# inclinometer-lcd-backpack.net
KiCad netlist of a schematic drawn in EAGLE
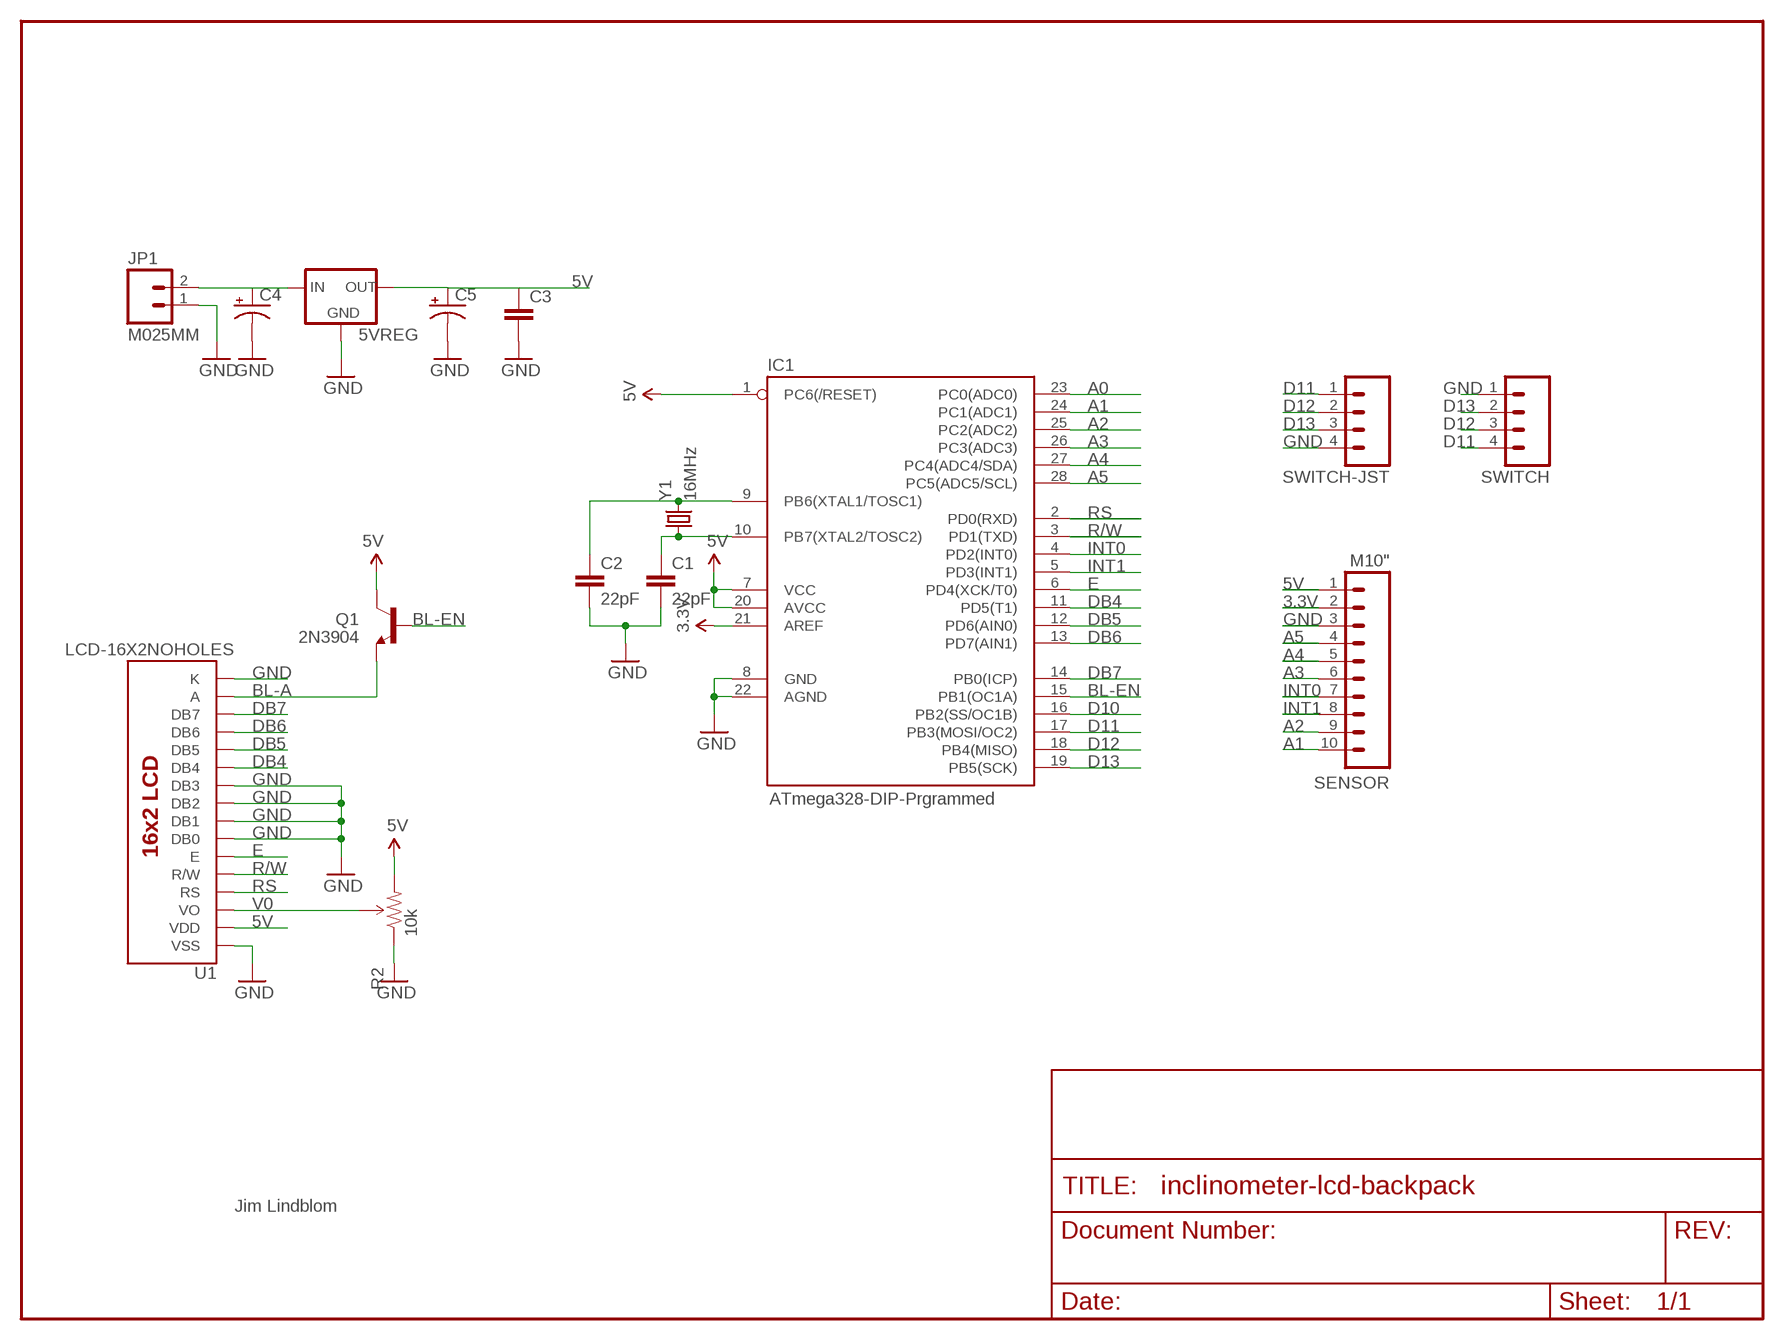
[diagram p0: schematic, sheet 1]

(export (version "E")
  (design (tool "Eeschema 10.0.6"))
  (components
    (comp (ref "5VREG")
      (value "78XXS")
      (footprint "eagle-import:78XXS")
      (libsource (lib "eagle-import") (part "78XXS"))
    )
    (comp (ref "C1")
      (value "22pF")
      (footprint "eagle-import:CAP-PTH-SMALL2")
      (libsource (lib "eagle-import") (part "CAPPTH2"))
    )
    (comp (ref "C2")
      (value "22pF")
      (footprint "eagle-import:CAP-PTH-SMALL2")
      (libsource (lib "eagle-import") (part "CAPPTH2"))
    )
    (comp (ref "C3")
      (value "CAPPTH2")
      (footprint "eagle-import:CAP-PTH-SMALL2")
      (libsource (lib "eagle-import") (part "SparkFun-Capacitors_CAPPTH2"))
    )
    (comp (ref "C4")
      (value "CAP_POLPTH2")
      (footprint "eagle-import:CPOL-RADIAL-10UF-25V")
      (libsource (lib "eagle-import") (part "CAP_POLPTH2"))
    )
    (comp (ref "C5")
      (value "CAP_POLPTH2")
      (footprint "eagle-import:CPOL-RADIAL-10UF-25V")
      (libsource (lib "eagle-import") (part "CAP_POLPTH2"))
    )
    (comp (ref "IC1")
      (value "ATmega328-DIP-Prgrammed")
      (footprint "eagle-import:DIL28-3")
      (libsource (lib "eagle-import") (part "AVR-MEGA8-PPTH"))
    )
    (comp (ref "JP1")
      (value "M025MM")
      (footprint "eagle-import:SCREWTERMINAL-5MM-2")
      (libsource (lib "eagle-import") (part "M025MM"))
    )
    (comp (ref "Q1")
      (value "2N3904")
      (footprint "eagle-import:TO-92")
      (libsource (lib "eagle-import") (part "TRANSISTOR_NPNTO92"))
    )
    (comp (ref "R2")
      (value "10k")
      (footprint "eagle-import:TRIM_POT_PTH")
      (libsource (lib "eagle-import") (part "TRIMPOTPTH"))
    )
    (comp (ref "SENSOR")
      (value "M10\"")
      (footprint "eagle-import:1X10")
      (libsource (lib "eagle-import") (part "M10{dblquote}"))
    )
    (comp (ref "SWITCH")
      (value "M04PTH")
      (footprint "eagle-import:1X04")
      (libsource (lib "eagle-import") (part "M04PTH"))
    )
    (comp (ref "SWITCH-JST")
      (value "M04JST-PTH")
      (footprint "eagle-import:JST-4-PTH")
      (libsource (lib "eagle-import") (part "M04JST-PTH"))
    )
    (comp (ref "U1")
      (value "LCD-16X2NOHOLES")
      (footprint "eagle-import:LCD-16X2_NOHOLES")
      (libsource (lib "eagle-import") (part "LCD-16X2NOHOLES"))
    )
    (comp (ref "Y1")
      (value "16MHz")
      (footprint "eagle-import:HC49US")
      (libsource (lib "eagle-import") (part "CRYSTALHC49US"))
    )
  )
  (nets
    (net (code "1") (name "/A0") (class "Default")
      (node (ref "IC1") (pin "23") (pinfunction "PC0(ADC0)_23") (pintype "bidirectional"))
    )
    (net (code "2") (name "/A1") (class "Default")
      (node (ref "IC1") (pin "24") (pinfunction "PC1(ADC1)_24") (pintype "bidirectional"))
      (node (ref "SENSOR") (pin "10") (pinfunction "10_10") (pintype "passive"))
    )
    (net (code "3") (name "/A2") (class "Default")
      (node (ref "IC1") (pin "25") (pinfunction "PC2(ADC2)_25") (pintype "bidirectional"))
      (node (ref "SENSOR") (pin "9") (pinfunction "9_9") (pintype "passive"))
    )
    (net (code "4") (name "/A3") (class "Default")
      (node (ref "IC1") (pin "26") (pinfunction "PC3(ADC3)_26") (pintype "bidirectional"))
      (node (ref "SENSOR") (pin "6") (pinfunction "6_6") (pintype "passive"))
    )
    (net (code "5") (name "/A4") (class "Default")
      (node (ref "IC1") (pin "27") (pinfunction "PC4(ADC4/SDA)_27") (pintype "bidirectional"))
      (node (ref "SENSOR") (pin "5") (pinfunction "5_5") (pintype "passive"))
    )
    (net (code "6") (name "/A5") (class "Default")
      (node (ref "IC1") (pin "28") (pinfunction "PC5(ADC5/SCL)_28") (pintype "bidirectional"))
      (node (ref "SENSOR") (pin "4") (pinfunction "4_4") (pintype "passive"))
    )
    (net (code "7") (name "/BL-A") (class "Default")
      (node (ref "Q1") (pin "1") (pinfunction "E_1") (pintype "passive"))
      (node (ref "U1") (pin "15") (pinfunction "A_15") (pintype "power_in"))
    )
    (net (code "8") (name "/BL-EN") (class "Default")
      (node (ref "IC1") (pin "15") (pinfunction "PB1(OC1A)_15") (pintype "bidirectional"))
      (node (ref "Q1") (pin "2") (pinfunction "B_2") (pintype "passive"))
    )
    (net (code "9") (name "/D10") (class "Default")
      (node (ref "IC1") (pin "16") (pinfunction "PB2(SS/OC1B)_16") (pintype "bidirectional"))
    )
    (net (code "10") (name "/D11") (class "Default")
      (node (ref "IC1") (pin "17") (pinfunction "PB3(MOSI/OC2)_17") (pintype "bidirectional"))
      (node (ref "SWITCH") (pin "4") (pinfunction "4_4") (pintype "passive"))
      (node (ref "SWITCH-JST") (pin "1") (pinfunction "1_1") (pintype "passive"))
    )
    (net (code "11") (name "/D12") (class "Default")
      (node (ref "IC1") (pin "18") (pinfunction "PB4(MISO)_18") (pintype "bidirectional"))
      (node (ref "SWITCH") (pin "3") (pinfunction "3_3") (pintype "passive"))
      (node (ref "SWITCH-JST") (pin "2") (pinfunction "2_2") (pintype "passive"))
    )
    (net (code "12") (name "/D13") (class "Default")
      (node (ref "IC1") (pin "19") (pinfunction "PB5(SCK)_19") (pintype "bidirectional"))
      (node (ref "SWITCH") (pin "2") (pinfunction "2_2") (pintype "passive"))
      (node (ref "SWITCH-JST") (pin "3") (pinfunction "3_3") (pintype "passive"))
    )
    (net (code "13") (name "/DB4") (class "Default")
      (node (ref "IC1") (pin "11") (pinfunction "PD5(T1)_11") (pintype "bidirectional"))
      (node (ref "U1") (pin "11") (pinfunction "DB4_11") (pintype "bidirectional"))
    )
    (net (code "14") (name "/DB5") (class "Default")
      (node (ref "IC1") (pin "12") (pinfunction "PD6(AIN0)_12") (pintype "bidirectional"))
      (node (ref "U1") (pin "12") (pinfunction "DB5_12") (pintype "bidirectional"))
    )
    (net (code "15") (name "/DB6") (class "Default")
      (node (ref "IC1") (pin "13") (pinfunction "PD7(AIN1)_13") (pintype "bidirectional"))
      (node (ref "U1") (pin "13") (pinfunction "DB6_13") (pintype "bidirectional"))
    )
    (net (code "16") (name "/DB7") (class "Default")
      (node (ref "IC1") (pin "14") (pinfunction "PB0(ICP)_14") (pintype "bidirectional"))
      (node (ref "U1") (pin "14") (pinfunction "DB7_14") (pintype "bidirectional"))
    )
    (net (code "17") (name "/E") (class "Default")
      (node (ref "IC1") (pin "6") (pinfunction "PD4(XCK/T0)_6") (pintype "bidirectional"))
      (node (ref "U1") (pin "6") (pinfunction "E_6") (pintype "input"))
    )
    (net (code "18") (name "/INT0") (class "Default")
      (node (ref "IC1") (pin "4") (pinfunction "PD2(INT0)_4") (pintype "bidirectional"))
      (node (ref "SENSOR") (pin "7") (pinfunction "7_7") (pintype "passive"))
    )
    (net (code "19") (name "/INT1") (class "Default")
      (node (ref "IC1") (pin "5") (pinfunction "PD3(INT1)_5") (pintype "bidirectional"))
      (node (ref "SENSOR") (pin "8") (pinfunction "8_8") (pintype "passive"))
    )
    (net (code "20") (name "/RS") (class "Default")
      (node (ref "IC1") (pin "2") (pinfunction "PD0(RXD)_2") (pintype "bidirectional"))
      (node (ref "U1") (pin "4") (pinfunction "RS_4") (pintype "input"))
    )
    (net (code "21") (name "/R{slash}W") (class "Default")
      (node (ref "IC1") (pin "3") (pinfunction "PD1(TXD)_3") (pintype "bidirectional"))
      (node (ref "U1") (pin "5") (pinfunction "R/W_5") (pintype "input"))
    )
    (net (code "22") (name "/V0") (class "Default")
      (node (ref "R2") (pin "2") (pinfunction "WIPER_2") (pintype "passive"))
      (node (ref "U1") (pin "3") (pinfunction "VO_3") (pintype "bidirectional"))
    )
    (net (code "23") (name "3.3V") (class "Default")
      (node (ref "IC1") (pin "21") (pinfunction "AREF_21") (pintype "bidirectional"))
      (node (ref "SENSOR") (pin "2") (pinfunction "2_2") (pintype "passive"))
    )
    (net (code "24") (name "5V") (class "Default")
      (node (ref "5VREG") (pin "OUT") (pinfunction "OUT_OUT") (pintype "passive"))
      (node (ref "C3") (pin "1") (pinfunction "1_1") (pintype "passive"))
      (node (ref "C5") (pin "1") (pinfunction "+_1") (pintype "passive"))
      (node (ref "IC1") (pin "1") (pinfunction "PC6(/RESET)_1") (pintype "bidirectional"))
      (node (ref "IC1") (pin "20") (pinfunction "AVCC_20") (pintype "bidirectional"))
      (node (ref "IC1") (pin "7") (pinfunction "VCC_7") (pintype "bidirectional"))
      (node (ref "Q1") (pin "3") (pinfunction "C_3") (pintype "passive"))
      (node (ref "R2") (pin "3") (pinfunction "CW_3") (pintype "passive"))
      (node (ref "SENSOR") (pin "1") (pinfunction "1_1") (pintype "passive"))
      (node (ref "U1") (pin "2") (pinfunction "VDD_2") (pintype "power_in"))
    )
    (net (code "25") (name "GND") (class "Default")
      (node (ref "5VREG") (pin "GND") (pinfunction "GND_GND") (pintype "input"))
      (node (ref "C1") (pin "2") (pinfunction "2_2") (pintype "passive"))
      (node (ref "C2") (pin "2") (pinfunction "2_2") (pintype "passive"))
      (node (ref "C3") (pin "2") (pinfunction "2_2") (pintype "passive"))
      (node (ref "C4") (pin "2") (pinfunction "-_2") (pintype "passive"))
      (node (ref "C5") (pin "2") (pinfunction "-_2") (pintype "passive"))
      (node (ref "IC1") (pin "22") (pinfunction "AGND_22") (pintype "bidirectional"))
      (node (ref "IC1") (pin "8") (pinfunction "GND_8") (pintype "bidirectional"))
      (node (ref "JP1") (pin "1") (pinfunction "1_1") (pintype "passive"))
      (node (ref "R2") (pin "1") (pinfunction "CCW_1") (pintype "passive"))
      (node (ref "SENSOR") (pin "3") (pinfunction "3_3") (pintype "passive"))
      (node (ref "SWITCH") (pin "1") (pinfunction "1_1") (pintype "passive"))
      (node (ref "SWITCH-JST") (pin "4") (pinfunction "4_4") (pintype "passive"))
      (node (ref "U1") (pin "1") (pinfunction "VSS_1") (pintype "power_in"))
      (node (ref "U1") (pin "10") (pinfunction "DB3_10") (pintype "bidirectional"))
      (node (ref "U1") (pin "16") (pinfunction "K_16") (pintype "power_in"))
      (node (ref "U1") (pin "7") (pinfunction "DB0_7") (pintype "bidirectional"))
      (node (ref "U1") (pin "8") (pinfunction "DB1_8") (pintype "bidirectional"))
      (node (ref "U1") (pin "9") (pinfunction "DB2_9") (pintype "bidirectional"))
    )
    (net (code "26") (name "Net-(C4-+)") (class "Default")
      (node (ref "5VREG") (pin "IN") (pinfunction "IN_IN") (pintype "input"))
      (node (ref "C4") (pin "1") (pinfunction "+_1") (pintype "passive"))
      (node (ref "JP1") (pin "2") (pinfunction "2_2") (pintype "passive"))
    )
    (net (code "27") (name "Net-(IC1-PB6(XTAL1{slash}TOSC1))") (class "Default")
      (node (ref "C2") (pin "1") (pinfunction "1_1") (pintype "passive"))
      (node (ref "IC1") (pin "9") (pinfunction "PB6(XTAL1/TOSC1)_9") (pintype "bidirectional"))
      (node (ref "Y1") (pin "2") (pinfunction "2_2") (pintype "passive"))
    )
    (net (code "28") (name "Net-(IC1-PB7(XTAL2{slash}TOSC2))") (class "Default")
      (node (ref "C1") (pin "1") (pinfunction "1_1") (pintype "passive"))
      (node (ref "IC1") (pin "10") (pinfunction "PB7(XTAL2/TOSC2)_10") (pintype "bidirectional"))
      (node (ref "Y1") (pin "1") (pinfunction "1_1") (pintype "passive"))
    )
  )
)
